# SortingHat.net
KiCad netlist of a schematic drawn in EAGLE
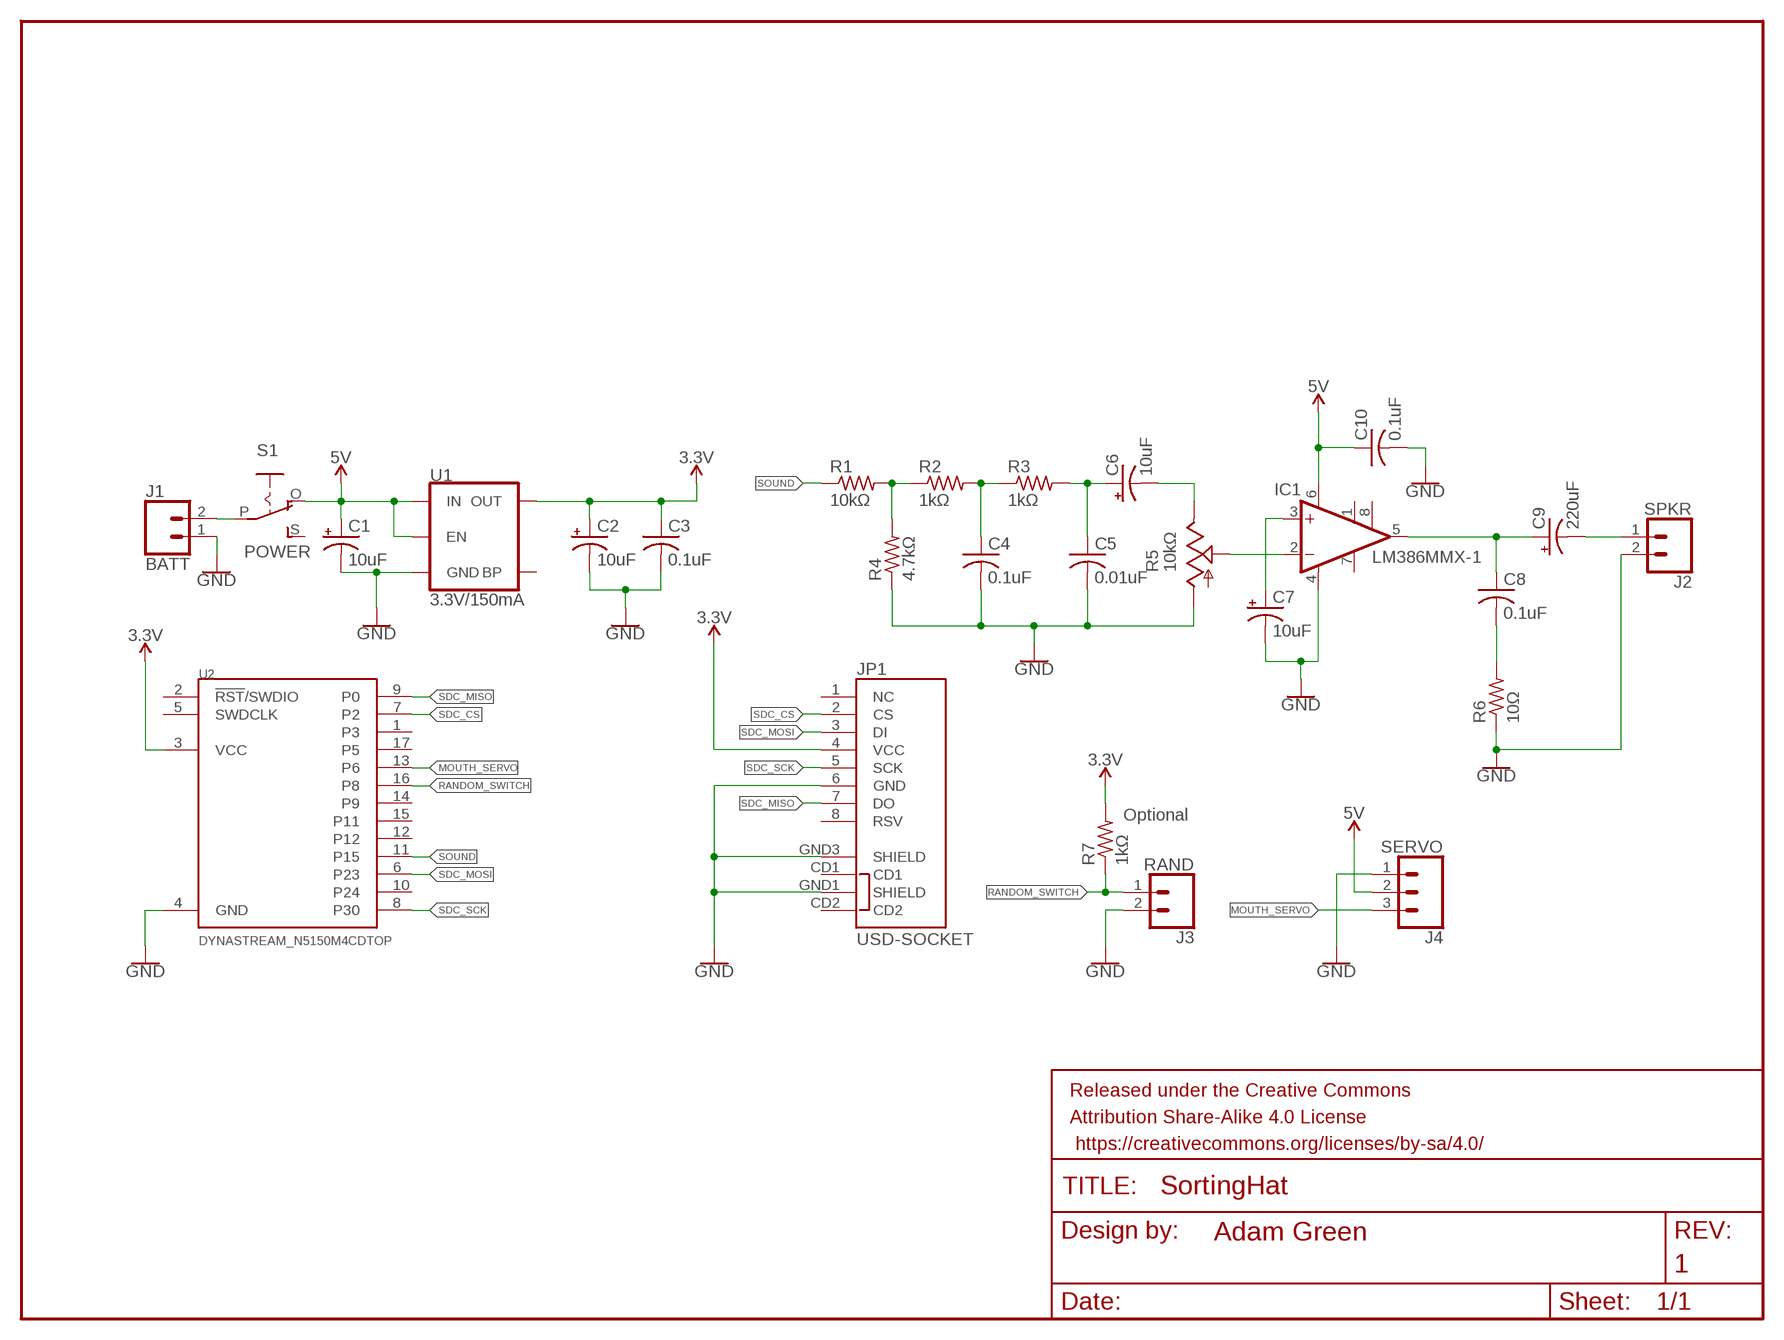
[diagram p0: schematic, sheet 1]

(export (version "E")
  (design (tool "Eeschema 10.0.6"))
  (components
    (comp (ref "C1")
      (value "10uF")
      (footprint "eagle-import:EIA3216")
      (libsource (lib "eagle-import") (part "10UF-POLAR-EIA3216-16V-10%(TANT)"))
    )
    (comp (ref "C2")
      (value "10uF")
      (footprint "eagle-import:EIA3216")
      (libsource (lib "eagle-import") (part "10UF-POLAR-EIA3216-16V-10%(TANT)"))
    )
    (comp (ref "C3")
      (value "0.1uF")
      (footprint "eagle-import:C0805")
      (libsource (lib "eagle-import") (part "C-USC0805"))
    )
    (comp (ref "C4")
      (value "0.1uF")
      (footprint "eagle-import:C0805")
      (libsource (lib "eagle-import") (part "C-USC0805"))
    )
    (comp (ref "C5")
      (value "0.01uF")
      (footprint "eagle-import:C0805")
      (libsource (lib "eagle-import") (part "C-USC0805"))
    )
    (comp (ref "C6")
      (value "10uF")
      (footprint "eagle-import:EIA3216")
      (libsource (lib "eagle-import") (part "10UF-POLAR-EIA3216-16V-10%(TANT)"))
    )
    (comp (ref "C7")
      (value "10uF")
      (footprint "eagle-import:EIA3216")
      (libsource (lib "eagle-import") (part "10UF-POLAR-EIA3216-16V-10%(TANT)"))
    )
    (comp (ref "C8")
      (value "0.1uF")
      (footprint "eagle-import:C0805")
      (libsource (lib "eagle-import") (part "C-USC0805"))
    )
    (comp (ref "C9")
      (value "220uF")
      (footprint "eagle-import:EIA3528")
      (libsource (lib "eagle-import") (part "68UF-POLAR-EIA3528-10V-10%(TANT)"))
    )
    (comp (ref "C10")
      (value "0.1uF")
      (footprint "eagle-import:C0805")
      (libsource (lib "eagle-import") (part "C-USC0805"))
    )
    (comp (ref "FRAME1")
      (value "FRAME-LETTER")
      (footprint "eagle-import:CREATIVE_COMMONS")
      (fields (field (name "DESIGNER") "Adam Green") (field (name "REV") "1"))
      (libsource (lib "eagle-import") (part "FRAME-LETTER"))
    )
    (comp (ref "IC1")
      (value "LM386MMX-1")
      (footprint "eagle-import:MMSOP08")
      (libsource (lib "eagle-import") (part "LM386?-MM1"))
    )
    (comp (ref "J1")
      (value "BATT")
      (footprint "eagle-import:1X02_NO_SILK")
      (libsource (lib "eagle-import") (part "CONN_021X02_NO_SILK"))
    )
    (comp (ref "J2")
      (value "SPKR")
      (footprint "eagle-import:1X02_NO_SILK")
      (libsource (lib "eagle-import") (part "CONN_021X02_NO_SILK"))
    )
    (comp (ref "J3")
      (value "RAND")
      (footprint "eagle-import:1X02_NO_SILK")
      (libsource (lib "eagle-import") (part "CONN_021X02_NO_SILK"))
    )
    (comp (ref "J4")
      (value "SERVO")
      (footprint "eagle-import:1X03_NO_SILK")
      (libsource (lib "eagle-import") (part "CONN_031X03_NO_SILK"))
    )
    (comp (ref "JP1")
      (value "USD-SOCKET")
      (footprint "eagle-import:MICROSD_1_1")
      (libsource (lib "eagle-import") (part "USD-SOCKET"))
    )
    (comp (ref "R1")
      (value "10kΩ")
      (footprint "eagle-import:R0805")
      (libsource (lib "eagle-import") (part "R-US_R0805"))
    )
    (comp (ref "R2")
      (value "1kΩ")
      (footprint "eagle-import:R0805")
      (libsource (lib "eagle-import") (part "R-US_R0805"))
    )
    (comp (ref "R3")
      (value "1kΩ")
      (footprint "eagle-import:R0805")
      (libsource (lib "eagle-import") (part "R-US_R0805"))
    )
    (comp (ref "R4")
      (value "4.7kΩ")
      (footprint "eagle-import:R0805")
      (libsource (lib "eagle-import") (part "R-US_R0805"))
    )
    (comp (ref "R5")
      (value "10kΩ")
      (footprint "eagle-import:3223W")
      (libsource (lib "eagle-import") (part "TRIM_US-3223W"))
    )
    (comp (ref "R6")
      (value "10Ω")
      (footprint "eagle-import:R0805")
      (libsource (lib "eagle-import") (part "R-US_R0805"))
    )
    (comp (ref "R7")
      (value "1kΩ")
      (footprint "eagle-import:R0805")
      (libsource (lib "eagle-import") (part "R-US_R0805"))
    )
    (comp (ref "S1")
      (value "POWER")
      (footprint "eagle-import:EG1218")
      (libsource (lib "eagle-import") (part "EG1218S"))
    )
    (comp (ref "U1")
      (value "3.3V/150mA")
      (footprint "eagle-import:SOT23-5")
      (libsource (lib "eagle-import") (part "V_REG_MIC52053.3V"))
    )
    (comp (ref "U2")
      (value "DYNASTREAM_N5150M4CDTOP")
      (footprint "eagle-import:N5150M4CD_TOP")
      (libsource (lib "eagle-import") (part "DYNASTREAM_N5150M4CDTOP"))
    )
  )
  (nets
    (net (code "1") (name "3.3V") (class "Default")
      (node (ref "C2") (pin "+") (pinfunction "+_+") (pintype "passive"))
      (node (ref "C3") (pin "1") (pinfunction "1_1") (pintype "passive"))
      (node (ref "JP1") (pin "4") (pinfunction "VCC_4") (pintype "bidirectional"))
      (node (ref "R7") (pin "2") (pinfunction "2_2") (pintype "passive"))
      (node (ref "U1") (pin "5") (pinfunction "OUT_5") (pintype "passive"))
      (node (ref "U2") (pin "3") (pinfunction "VCC_3") (pintype "power_in"))
    )
    (net (code "2") (name "5V") (class "Default")
      (node (ref "C1") (pin "+") (pinfunction "+_+") (pintype "passive"))
      (node (ref "C10") (pin "1") (pinfunction "1_1") (pintype "passive"))
      (node (ref "IC1") (pin "6") (pinfunction "VS_6") (pintype "power_in"))
      (node (ref "J4") (pin "2") (pinfunction "2_2") (pintype "passive"))
      (node (ref "S1") (pin "O") (pinfunction "O_O") (pintype "passive"))
      (node (ref "U1") (pin "1") (pinfunction "IN_1") (pintype "input"))
      (node (ref "U1") (pin "3") (pinfunction "EN_3") (pintype "input"))
    )
    (net (code "3") (name "GND") (class "Default")
      (node (ref "C1") (pin "-") (pinfunction "-_-") (pintype "passive"))
      (node (ref "C10") (pin "2") (pinfunction "2_2") (pintype "passive"))
      (node (ref "C2") (pin "-") (pinfunction "-_-") (pintype "passive"))
      (node (ref "C3") (pin "2") (pinfunction "2_2") (pintype "passive"))
      (node (ref "C4") (pin "2") (pinfunction "2_2") (pintype "passive"))
      (node (ref "C5") (pin "2") (pinfunction "2_2") (pintype "passive"))
      (node (ref "C7") (pin "-") (pinfunction "-_-") (pintype "passive"))
      (node (ref "IC1") (pin "4") (pinfunction "GND_4") (pintype "power_in"))
      (node (ref "J1") (pin "1") (pinfunction "1_1") (pintype "passive"))
      (node (ref "J2") (pin "2") (pinfunction "2_2") (pintype "passive"))
      (node (ref "J3") (pin "2") (pinfunction "2_2") (pintype "passive"))
      (node (ref "J4") (pin "1") (pinfunction "1_1") (pintype "passive"))
      (node (ref "JP1") (pin "6") (pinfunction "GND_6") (pintype "bidirectional"))
      (node (ref "JP1") (pin "GND1") (pinfunction "SHIELD_GND1") (pintype "bidirectional"))
      (node (ref "JP1") (pin "GND3") (pinfunction "SHIELD_GND3") (pintype "bidirectional"))
      (node (ref "R4") (pin "1") (pinfunction "1_1") (pintype "passive"))
      (node (ref "R5") (pin "1") (pinfunction "A_1") (pintype "passive"))
      (node (ref "R6") (pin "1") (pinfunction "1_1") (pintype "passive"))
      (node (ref "U1") (pin "2") (pinfunction "GND_2") (pintype "input"))
      (node (ref "U2") (pin "4") (pinfunction "GND_4") (pintype "power_in"))
    )
    (net (code "4") (name "MOUTH_SERVO") (class "Default")
      (node (ref "J4") (pin "3") (pinfunction "3_3") (pintype "passive"))
      (node (ref "U2") (pin "13") (pinfunction "P6_13") (pintype "bidirectional"))
    )
    (net (code "5") (name "Net-(C4-Pad1)") (class "Default")
      (node (ref "C4") (pin "1") (pinfunction "1_1") (pintype "passive"))
      (node (ref "R2") (pin "2") (pinfunction "2_2") (pintype "passive"))
      (node (ref "R3") (pin "1") (pinfunction "1_1") (pintype "passive"))
    )
    (net (code "6") (name "Net-(C5-Pad1)") (class "Default")
      (node (ref "C5") (pin "1") (pinfunction "1_1") (pintype "passive"))
      (node (ref "C6") (pin "+") (pinfunction "+_+") (pintype "passive"))
      (node (ref "R3") (pin "2") (pinfunction "2_2") (pintype "passive"))
    )
    (net (code "7") (name "Net-(C8-Pad2)") (class "Default")
      (node (ref "C8") (pin "2") (pinfunction "2_2") (pintype "passive"))
      (node (ref "R6") (pin "2") (pinfunction "2_2") (pintype "passive"))
    )
    (net (code "8") (name "Net-(C9-+)") (class "Default")
      (node (ref "C8") (pin "1") (pinfunction "1_1") (pintype "passive"))
      (node (ref "C9") (pin "A") (pinfunction "+_A") (pintype "passive"))
      (node (ref "IC1") (pin "5") (pinfunction "OUT_5") (pintype "output"))
    )
    (net (code "9") (name "Net-(C9--)") (class "Default")
      (node (ref "C9") (pin "C") (pinfunction "-_C") (pintype "passive"))
      (node (ref "J2") (pin "1") (pinfunction "1_1") (pintype "passive"))
    )
    (net (code "10") (name "Net-(IC1-+IN)") (class "Default")
      (node (ref "C7") (pin "+") (pinfunction "+_+") (pintype "passive"))
      (node (ref "IC1") (pin "3") (pinfunction "+IN_3") (pintype "input"))
    )
    (net (code "11") (name "Net-(IC1--IN)") (class "Default")
      (node (ref "IC1") (pin "2") (pinfunction "-IN_2") (pintype "input"))
      (node (ref "R5") (pin "2") (pinfunction "S_2") (pintype "passive"))
    )
    (net (code "12") (name "Net-(J1-Pad2)") (class "Default")
      (node (ref "J1") (pin "2") (pinfunction "2_2") (pintype "passive"))
      (node (ref "S1") (pin "P") (pinfunction "P_P") (pintype "passive"))
    )
    (net (code "13") (name "Net-(R1-Pad2)") (class "Default")
      (node (ref "R1") (pin "2") (pinfunction "2_2") (pintype "passive"))
      (node (ref "R2") (pin "1") (pinfunction "1_1") (pintype "passive"))
      (node (ref "R4") (pin "2") (pinfunction "2_2") (pintype "passive"))
    )
    (net (code "14") (name "Net-(R5-E)") (class "Default")
      (node (ref "C6") (pin "-") (pinfunction "-_-") (pintype "passive"))
      (node (ref "R5") (pin "3") (pinfunction "E_3") (pintype "passive"))
    )
    (net (code "15") (name "RANDOM_SWITCH") (class "Default")
      (node (ref "J3") (pin "1") (pinfunction "1_1") (pintype "passive"))
      (node (ref "R7") (pin "1") (pinfunction "1_1") (pintype "passive"))
      (node (ref "U2") (pin "16") (pinfunction "P8_16") (pintype "bidirectional"))
    )
    (net (code "16") (name "SDC_CS") (class "Default")
      (node (ref "JP1") (pin "2") (pinfunction "CS_2") (pintype "bidirectional"))
      (node (ref "U2") (pin "7") (pinfunction "P2_7") (pintype "bidirectional"))
    )
    (net (code "17") (name "SDC_MISO") (class "Default")
      (node (ref "JP1") (pin "7") (pinfunction "DO_7") (pintype "bidirectional"))
      (node (ref "U2") (pin "9") (pinfunction "P0_9") (pintype "bidirectional"))
    )
    (net (code "18") (name "SDC_MOSI") (class "Default")
      (node (ref "JP1") (pin "3") (pinfunction "DI_3") (pintype "bidirectional"))
      (node (ref "U2") (pin "6") (pinfunction "P23_6") (pintype "bidirectional"))
    )
    (net (code "19") (name "SDC_SCK") (class "Default")
      (node (ref "JP1") (pin "5") (pinfunction "SCK_5") (pintype "bidirectional"))
      (node (ref "U2") (pin "8") (pinfunction "P30_8") (pintype "bidirectional"))
    )
    (net (code "20") (name "SOUND") (class "Default")
      (node (ref "R1") (pin "1") (pinfunction "1_1") (pintype "passive"))
      (node (ref "U2") (pin "11") (pinfunction "P15_11") (pintype "bidirectional"))
    )
    (net (code "21") (name "unconnected-(IC1-BYPASS-Pad7)") (class "Default")
      (node (ref "IC1") (pin "7") (pinfunction "BYPASS_7") (pintype "passive"))
    )
    (net (code "22") (name "unconnected-(IC1-GAIN-Pad1)") (class "Default")
      (node (ref "IC1") (pin "1") (pinfunction "GAIN_1") (pintype "passive"))
    )
    (net (code "23") (name "unconnected-(IC1-GAIN-Pad8)") (class "Default")
      (node (ref "IC1") (pin "8") (pinfunction "GAIN_8") (pintype "passive"))
    )
    (net (code "24") (name "unconnected-(JP1-NC-Pad1)") (class "Default")
      (node (ref "JP1") (pin "1") (pinfunction "NC_1") (pintype "bidirectional"))
    )
    (net (code "25") (name "unconnected-(JP1-PadCD1)") (class "Default")
      (node (ref "JP1") (pin "CD1") (pinfunction "CD1_CD1") (pintype "bidirectional"))
    )
    (net (code "26") (name "unconnected-(JP1-PadCD2)") (class "Default")
      (node (ref "JP1") (pin "CD2") (pinfunction "CD2_CD2") (pintype "bidirectional"))
    )
    (net (code "27") (name "unconnected-(JP1-RSV-Pad8)") (class "Default")
      (node (ref "JP1") (pin "8") (pinfunction "RSV_8") (pintype "bidirectional"))
    )
    (net (code "28") (name "unconnected-(S1-PadS)") (class "Default")
      (node (ref "S1") (pin "S") (pinfunction "S_S") (pintype "passive"))
    )
    (net (code "29") (name "unconnected-(U1-BP-Pad4)") (class "Default")
      (node (ref "U1") (pin "4") (pinfunction "BP_4") (pintype "input"))
    )
    (net (code "30") (name "unconnected-(U2-P3-Pad1)") (class "Default")
      (node (ref "U2") (pin "1") (pinfunction "P3_1") (pintype "bidirectional"))
    )
    (net (code "31") (name "unconnected-(U2-P5-Pad17)") (class "Default")
      (node (ref "U2") (pin "17") (pinfunction "P5_17") (pintype "bidirectional"))
    )
    (net (code "32") (name "unconnected-(U2-P9-Pad14)") (class "Default")
      (node (ref "U2") (pin "14") (pinfunction "P9_14") (pintype "bidirectional"))
    )
    (net (code "33") (name "unconnected-(U2-P11-Pad15)") (class "Default")
      (node (ref "U2") (pin "15") (pinfunction "P11_15") (pintype "bidirectional"))
    )
    (net (code "34") (name "unconnected-(U2-P12-Pad12)") (class "Default")
      (node (ref "U2") (pin "12") (pinfunction "P12_12") (pintype "bidirectional"))
    )
    (net (code "35") (name "unconnected-(U2-P24-Pad10)") (class "Default")
      (node (ref "U2") (pin "10") (pinfunction "P24_10") (pintype "bidirectional"))
    )
    (net (code "36") (name "unconnected-(U2-SWDCLK-Pad5)") (class "Default")
      (node (ref "U2") (pin "5") (pinfunction "SWDCLK_5") (pintype "input"))
    )
    (net (code "37") (name "unconnected-(U2-~{RST}{slash}SWDIO-Pad2)") (class "Default")
      (node (ref "U2") (pin "2") (pinfunction "~{RST}/SWDIO_2") (pintype "bidirectional"))
    )
  )
)
